# SCH_Poultry-Farm-Prediction-Models-_Fiel.net
KiCad netlist of a schematic drawn in EasyEDA
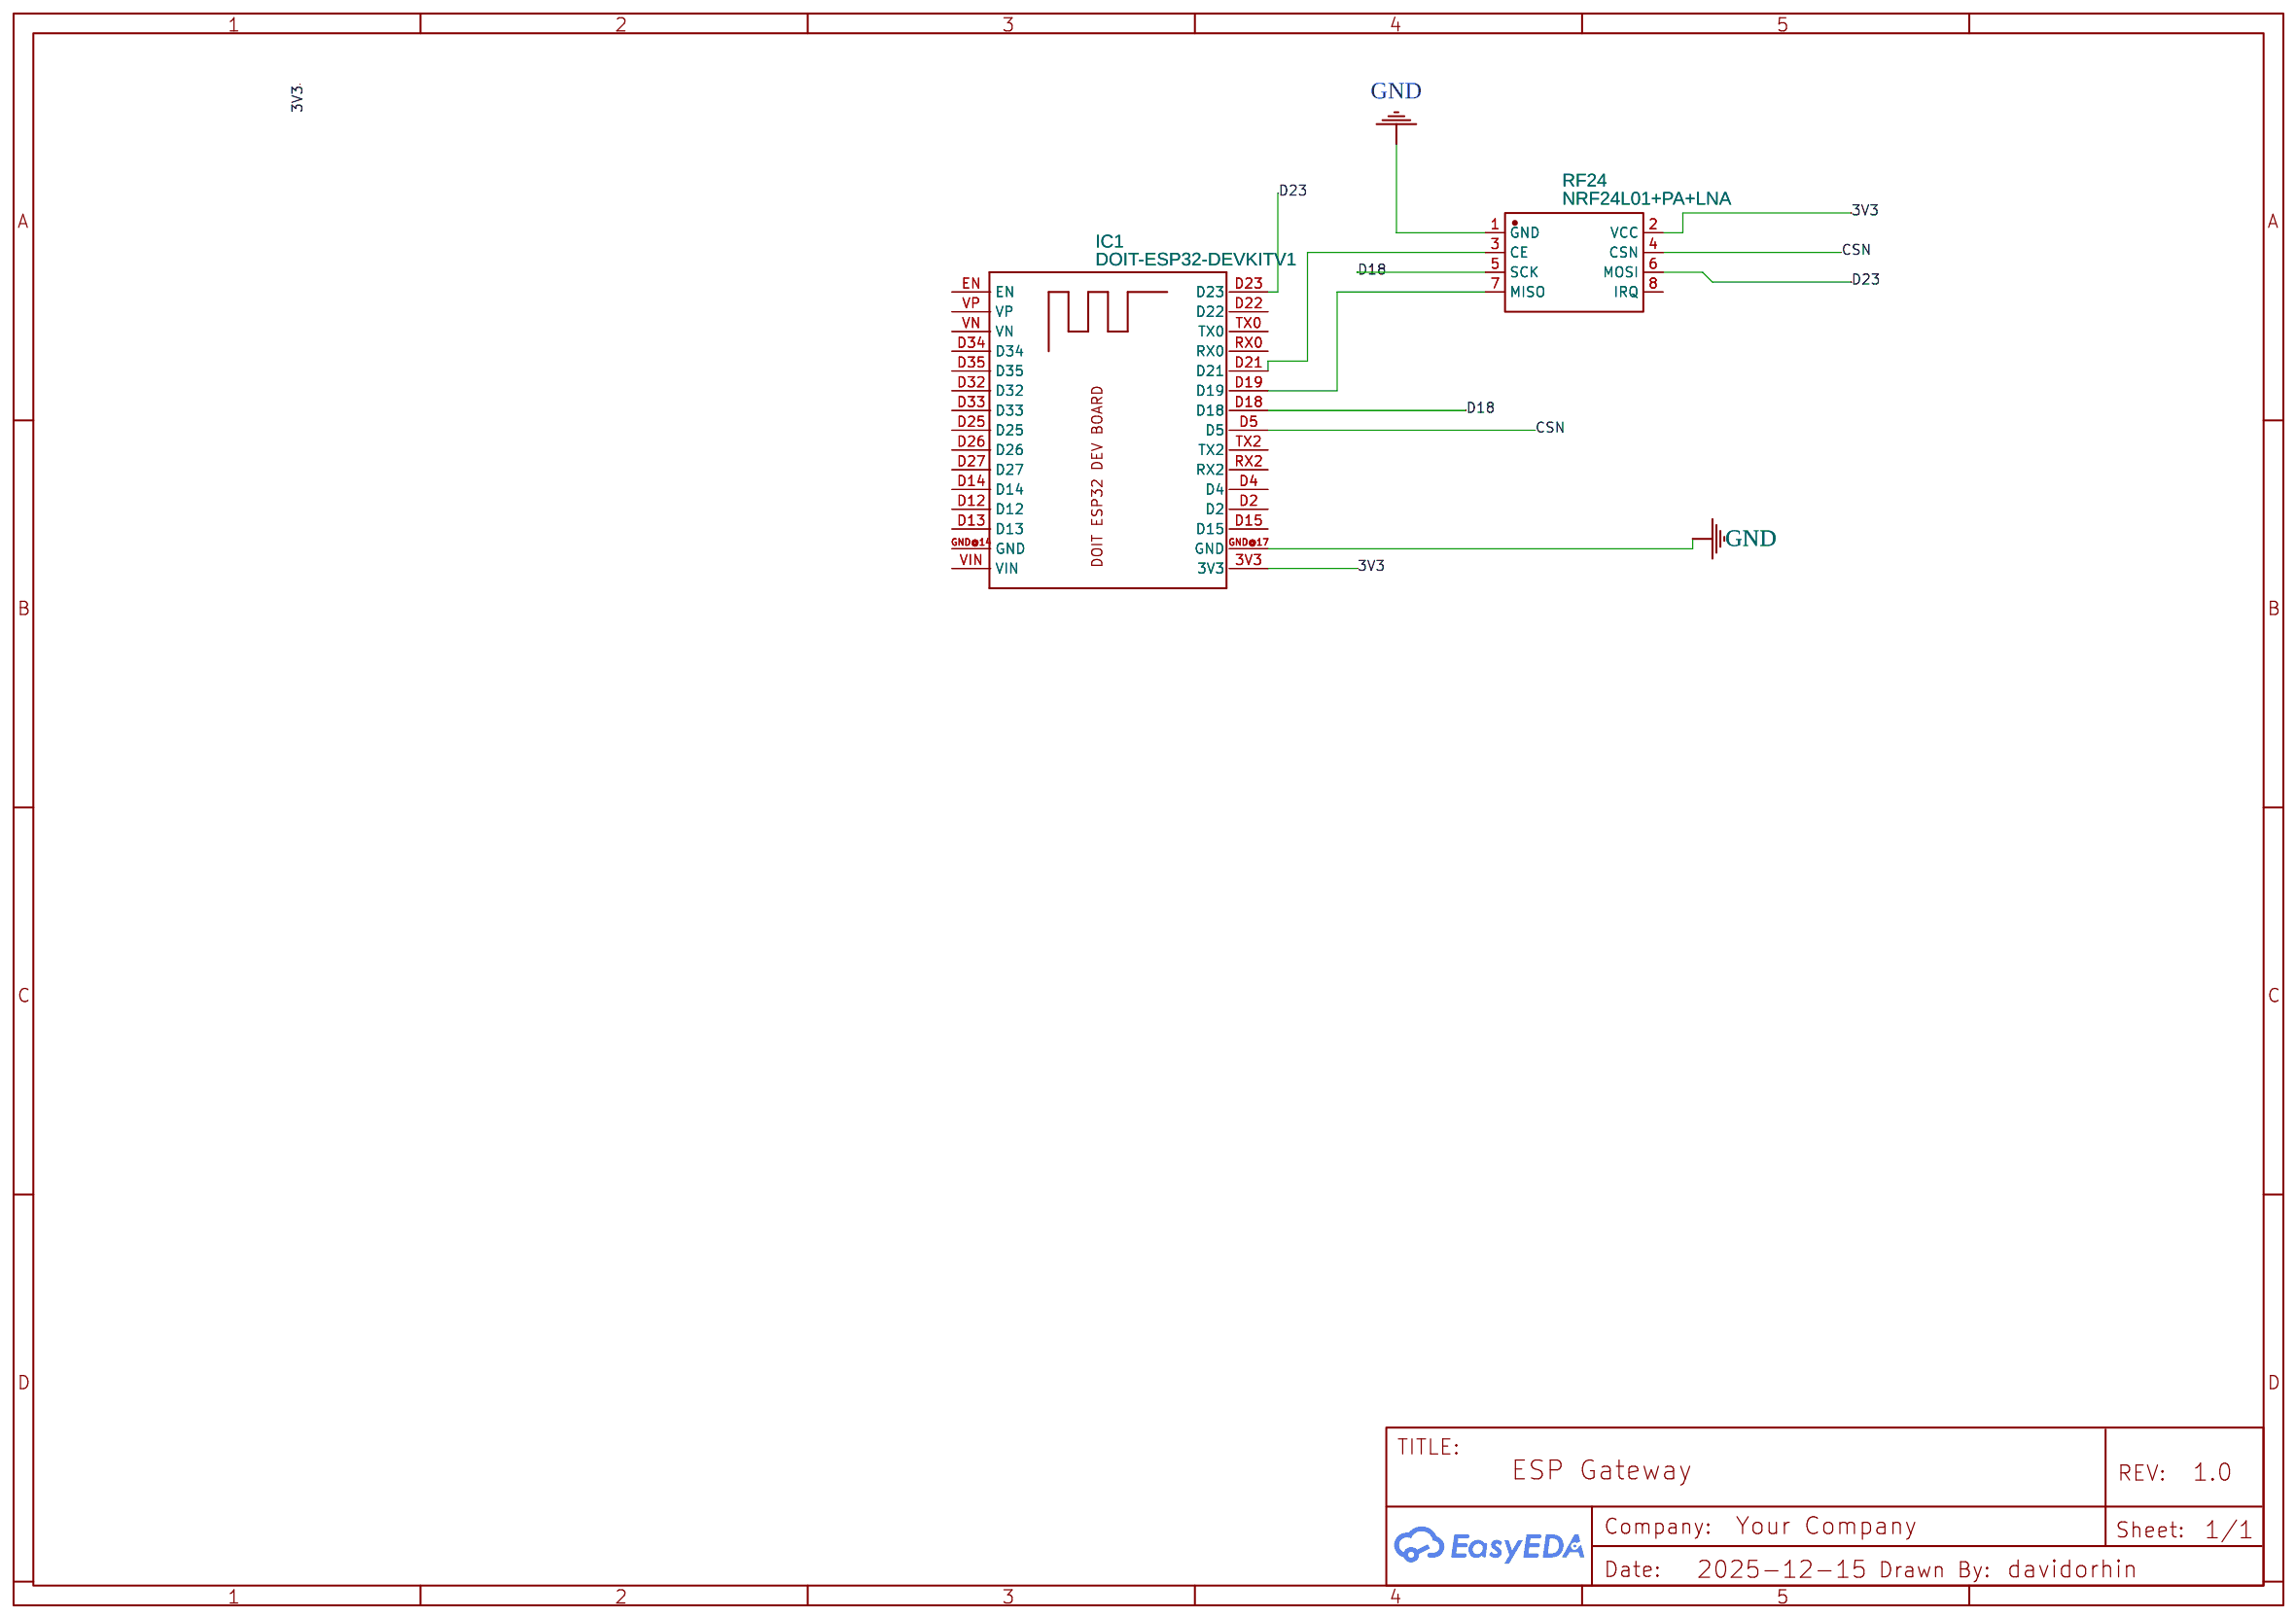
[diagram p0: Gateway Esp 32]
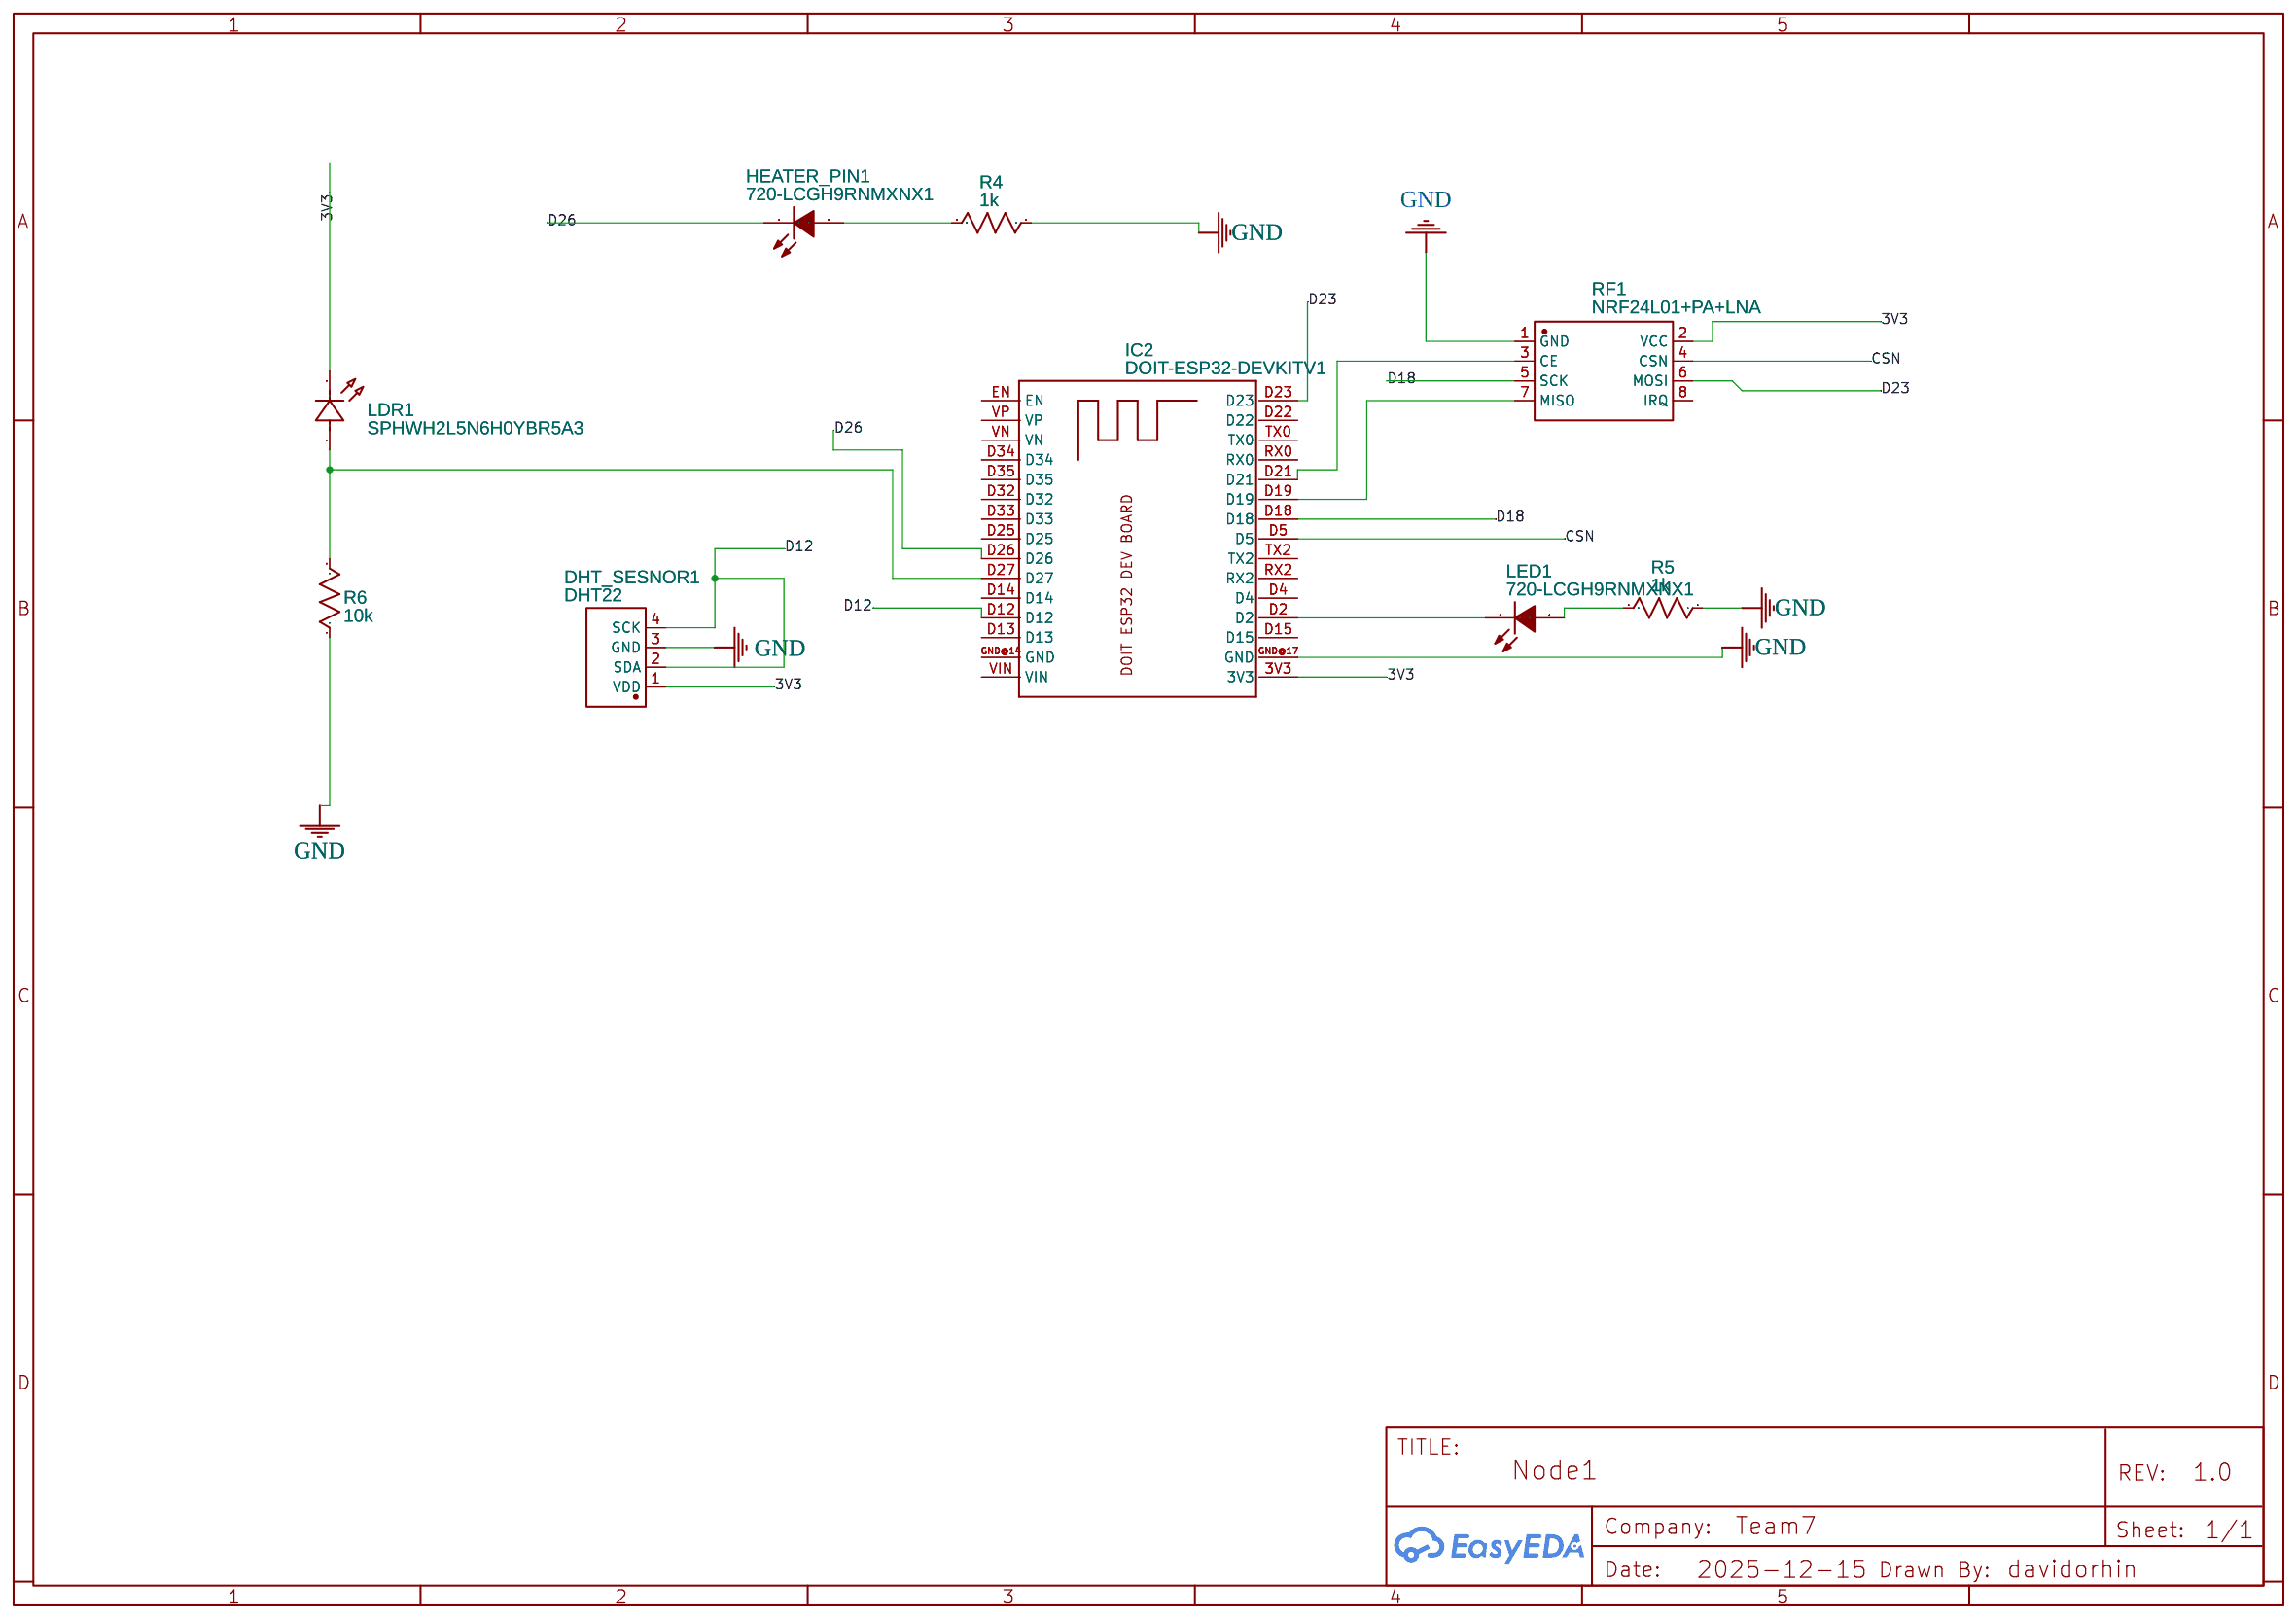
[diagram p1: Field Nodes Esp 33]

(export (version "E")
  (design (tool "Eeschema 10.0.6"))
  (components
    (comp (ref "IC1") (value "DOIT-ESP32-DEVKITV1") (libsource (lib "") (part "DOIT-ESP32-DEVKITV1")))
    (comp (ref "RF24")
      (value "NRF24L01+PA+LNA")
      (fields (field (name "Manufacturer Part") "nRF24L01+PA+LNA"))
      (libsource (lib "") (part "NRF24L01+PA+LNA"))
    )
    (comp (ref "DHT_SESNOR1")
      (value "DHT22")
      (fields (field (name "Manufacturer") "HAIGU(广州海谷)"))
      (libsource (lib "") (part "DHT22"))
    )
    (comp (ref "HEATER_PIN1") (value "720-LCGH9RNMXNX1") (libsource (lib "") (part "720-LCGH9RNMXNX1_1")))
    (comp (ref "IC2") (value "DOIT-ESP32-DEVKITV1") (libsource (lib "") (part "DOIT-ESP32-DEVKITV1")))
    (comp (ref "LDR1")
      (value "SPHWH2L5N6H0YBR5A3")
      (fields (field (name "Manufacturer") "SAMSUNG(三星)"))
      (libsource (lib "") (part "SPHWH2L5N6H0YBR5A3"))
    )
    (comp (ref "LED1") (value "720-LCGH9RNMXNX1") (libsource (lib "") (part "720-LCGH9RNMXNX1")))
    (comp (ref "R4") (value "1k") (libsource (lib "") (part "R_0603_US_1")))
    (comp (ref "R5") (value "1k") (libsource (lib "") (part "R_0603_US_1")))
    (comp (ref "R6") (value "10k") (libsource (lib "") (part "R_0603_US")))
    (comp (ref "RF1")
      (value "NRF24L01+PA+LNA")
      (fields (field (name "Manufacturer Part") "nRF24L01+PA+LNA"))
      (libsource (lib "") (part "NRF24L01+PA+LNA"))
    )
  )
  (nets
    (net (code "1") (name "3V3") (class "Default")
      (node (ref "DHT_SESNOR1") (pin "1") (pinfunction "VDD_1") (pintype "unspecified"))
      (node (ref "IC1") (pin "3V3") (pinfunction "3V3_3V3") (pintype "bidirectional"))
      (node (ref "IC2") (pin "3V3") (pinfunction "3V3_3V3") (pintype "bidirectional"))
      (node (ref "LDR1") (pin "1") (pinfunction "C_1") (pintype "unspecified"))
      (node (ref "RF1") (pin "2") (pinfunction "VCC_2") (pintype "unspecified"))
      (node (ref "RF24") (pin "2") (pinfunction "VCC_2") (pintype "unspecified"))
    )
    (net (code "2") (name "CSN") (class "Default")
      (node (ref "IC1") (pin "D5") (pinfunction "D5_D5") (pintype "bidirectional"))
      (node (ref "IC2") (pin "D5") (pinfunction "D5_D5") (pintype "bidirectional"))
      (node (ref "RF1") (pin "4") (pinfunction "CSN_4") (pintype "unspecified"))
      (node (ref "RF24") (pin "4") (pinfunction "CSN_4") (pintype "unspecified"))
    )
    (net (code "3") (name "D12") (class "Default")
      (node (ref "DHT_SESNOR1") (pin "2") (pinfunction "SDA_2") (pintype "unspecified"))
      (node (ref "DHT_SESNOR1") (pin "4") (pinfunction "SCK_4") (pintype "unspecified"))
      (node (ref "IC2") (pin "D12") (pinfunction "D12_D12") (pintype "bidirectional"))
    )
    (net (code "4") (name "D18") (class "Default")
      (node (ref "IC1") (pin "D18") (pinfunction "D18_D18") (pintype "bidirectional"))
      (node (ref "IC2") (pin "D18") (pinfunction "D18_D18") (pintype "bidirectional"))
      (node (ref "RF1") (pin "5") (pinfunction "SCK_5") (pintype "unspecified"))
      (node (ref "RF24") (pin "5") (pinfunction "SCK_5") (pintype "unspecified"))
    )
    (net (code "5") (name "D23") (class "Default")
      (node (ref "IC1") (pin "D23") (pinfunction "D23_D23") (pintype "bidirectional"))
      (node (ref "IC2") (pin "D23") (pinfunction "D23_D23") (pintype "bidirectional"))
      (node (ref "RF1") (pin "6") (pinfunction "MOSI_6") (pintype "unspecified"))
      (node (ref "RF24") (pin "6") (pinfunction "MOSI_6") (pintype "unspecified"))
    )
    (net (code "6") (name "D26") (class "Default")
      (node (ref "HEATER_PIN1") (pin "1") (pinfunction "K_1") (pintype "unspecified"))
      (node (ref "IC2") (pin "D26") (pinfunction "D26_D26") (pintype "bidirectional"))
    )
    (net (code "7") (name "GND") (class "Default")
      (node (ref "DHT_SESNOR1") (pin "3") (pinfunction "GND_3") (pintype "unspecified"))
      (node (ref "IC1") (pin "GND@17") (pinfunction "GND_GND@17") (pintype "bidirectional"))
      (node (ref "IC2") (pin "GND@17") (pinfunction "GND_GND@17") (pintype "bidirectional"))
      (node (ref "R4") (pin "1") (pinfunction "1_1") (pintype "unspecified"))
      (node (ref "R5") (pin "1") (pinfunction "1_1") (pintype "unspecified"))
      (node (ref "R6") (pin "1") (pinfunction "1_1") (pintype "unspecified"))
      (node (ref "RF1") (pin "1") (pinfunction "GND_1") (pintype "unspecified"))
      (node (ref "RF24") (pin "1") (pinfunction "GND_1") (pintype "unspecified"))
    )
    (net (code "8") (name "Net-(HEATER_PIN1-A)") (class "Default")
      (node (ref "HEATER_PIN1") (pin "2") (pinfunction "A_2") (pintype "unspecified"))
      (node (ref "R4") (pin "2") (pinfunction "2_2") (pintype "unspecified"))
    )
    (net (code "9") (name "Net-(LDR1-A)") (class "Default")
      (node (ref "IC2") (pin "D27") (pinfunction "D27_D27") (pintype "bidirectional"))
      (node (ref "LDR1") (pin "2") (pinfunction "A_2") (pintype "unspecified"))
      (node (ref "R6") (pin "2") (pinfunction "2_2") (pintype "unspecified"))
    )
    (net (code "10") (name "Net-(LED1-A)") (class "Default")
      (node (ref "LED1") (pin "2") (pinfunction "A_2") (pintype "unspecified"))
      (node (ref "R5") (pin "2") (pinfunction "2_2") (pintype "unspecified"))
    )
    (net (code "11") (name "Net-(LED1-K)") (class "Default")
      (node (ref "IC2") (pin "D2") (pinfunction "D2_D2") (pintype "bidirectional"))
      (node (ref "LED1") (pin "1") (pinfunction "K_1") (pintype "unspecified"))
    )
    (net (code "12") (name "Net-(RF1-CE)") (class "Default")
      (node (ref "IC2") (pin "D21") (pinfunction "D21_D21") (pintype "bidirectional"))
      (node (ref "RF1") (pin "3") (pinfunction "CE_3") (pintype "unspecified"))
    )
    (net (code "13") (name "Net-(RF1-MISO)") (class "Default")
      (node (ref "IC2") (pin "D19") (pinfunction "D19_D19") (pintype "bidirectional"))
      (node (ref "RF1") (pin "7") (pinfunction "MISO_7") (pintype "unspecified"))
    )
    (net (code "14") (name "Net-(RF24-CE)") (class "Default")
      (node (ref "IC1") (pin "D21") (pinfunction "D21_D21") (pintype "bidirectional"))
      (node (ref "RF24") (pin "3") (pinfunction "CE_3") (pintype "unspecified"))
    )
    (net (code "15") (name "Net-(RF24-MISO)") (class "Default")
      (node (ref "IC1") (pin "D19") (pinfunction "D19_D19") (pintype "bidirectional"))
      (node (ref "RF24") (pin "7") (pinfunction "MISO_7") (pintype "unspecified"))
    )
    (net (code "16") (name "unconnected-(IC1-GND-PadGND@14)") (class "Default")
      (node (ref "IC1") (pin "GND@14") (pinfunction "GND_GND@14") (pintype "bidirectional"))
    )
    (net (code "17") (name "unconnected-(IC1-PadD2)") (class "Default")
      (node (ref "IC1") (pin "D2") (pinfunction "D2_D2") (pintype "bidirectional"))
    )
    (net (code "18") (name "unconnected-(IC1-PadD4)") (class "Default")
      (node (ref "IC1") (pin "D4") (pinfunction "D4_D4") (pintype "bidirectional"))
    )
    (net (code "19") (name "unconnected-(IC1-PadD12)") (class "Default")
      (node (ref "IC1") (pin "D12") (pinfunction "D12_D12") (pintype "bidirectional"))
    )
    (net (code "20") (name "unconnected-(IC1-PadD13)") (class "Default")
      (node (ref "IC1") (pin "D13") (pinfunction "D13_D13") (pintype "bidirectional"))
    )
    (net (code "21") (name "unconnected-(IC1-PadD14)") (class "Default")
      (node (ref "IC1") (pin "D14") (pinfunction "D14_D14") (pintype "bidirectional"))
    )
    (net (code "22") (name "unconnected-(IC1-PadD15)") (class "Default")
      (node (ref "IC1") (pin "D15") (pinfunction "D15_D15") (pintype "bidirectional"))
    )
    (net (code "23") (name "unconnected-(IC1-PadD22)") (class "Default")
      (node (ref "IC1") (pin "D22") (pinfunction "D22_D22") (pintype "bidirectional"))
    )
    (net (code "24") (name "unconnected-(IC1-PadD25)") (class "Default")
      (node (ref "IC1") (pin "D25") (pinfunction "D25_D25") (pintype "bidirectional"))
    )
    (net (code "25") (name "unconnected-(IC1-PadD26)") (class "Default")
      (node (ref "IC1") (pin "D26") (pinfunction "D26_D26") (pintype "bidirectional"))
    )
    (net (code "26") (name "unconnected-(IC1-PadD27)") (class "Default")
      (node (ref "IC1") (pin "D27") (pinfunction "D27_D27") (pintype "bidirectional"))
    )
    (net (code "27") (name "unconnected-(IC1-PadD32)") (class "Default")
      (node (ref "IC1") (pin "D32") (pinfunction "D32_D32") (pintype "bidirectional"))
    )
    (net (code "28") (name "unconnected-(IC1-PadD33)") (class "Default")
      (node (ref "IC1") (pin "D33") (pinfunction "D33_D33") (pintype "bidirectional"))
    )
    (net (code "29") (name "unconnected-(IC1-PadD34)") (class "Default")
      (node (ref "IC1") (pin "D34") (pinfunction "D34_D34") (pintype "bidirectional"))
    )
    (net (code "30") (name "unconnected-(IC1-PadD35)") (class "Default")
      (node (ref "IC1") (pin "D35") (pinfunction "D35_D35") (pintype "bidirectional"))
    )
    (net (code "31") (name "unconnected-(IC1-PadEN)") (class "Default")
      (node (ref "IC1") (pin "EN") (pinfunction "EN_EN") (pintype "bidirectional"))
    )
    (net (code "32") (name "unconnected-(IC1-PadRX0)") (class "Default")
      (node (ref "IC1") (pin "RX0") (pinfunction "RX0_RX0") (pintype "bidirectional"))
    )
    (net (code "33") (name "unconnected-(IC1-PadRX2)") (class "Default")
      (node (ref "IC1") (pin "RX2") (pinfunction "RX2_RX2") (pintype "bidirectional"))
    )
    (net (code "34") (name "unconnected-(IC1-PadTX0)") (class "Default")
      (node (ref "IC1") (pin "TX0") (pinfunction "TX0_TX0") (pintype "bidirectional"))
    )
    (net (code "35") (name "unconnected-(IC1-PadTX2)") (class "Default")
      (node (ref "IC1") (pin "TX2") (pinfunction "TX2_TX2") (pintype "bidirectional"))
    )
    (net (code "36") (name "unconnected-(IC1-PadVIN)") (class "Default")
      (node (ref "IC1") (pin "VIN") (pinfunction "VIN_VIN") (pintype "bidirectional"))
    )
    (net (code "37") (name "unconnected-(IC1-PadVN)") (class "Default")
      (node (ref "IC1") (pin "VN") (pinfunction "VN_VN") (pintype "bidirectional"))
    )
    (net (code "38") (name "unconnected-(IC1-PadVP)") (class "Default")
      (node (ref "IC1") (pin "VP") (pinfunction "VP_VP") (pintype "bidirectional"))
    )
    (net (code "39") (name "unconnected-(IC2-GND-PadGND@14)") (class "Default")
      (node (ref "IC2") (pin "GND@14") (pinfunction "GND_GND@14") (pintype "bidirectional"))
    )
    (net (code "40") (name "unconnected-(IC2-PadD4)") (class "Default")
      (node (ref "IC2") (pin "D4") (pinfunction "D4_D4") (pintype "bidirectional"))
    )
    (net (code "41") (name "unconnected-(IC2-PadD13)") (class "Default")
      (node (ref "IC2") (pin "D13") (pinfunction "D13_D13") (pintype "bidirectional"))
    )
    (net (code "42") (name "unconnected-(IC2-PadD14)") (class "Default")
      (node (ref "IC2") (pin "D14") (pinfunction "D14_D14") (pintype "bidirectional"))
    )
    (net (code "43") (name "unconnected-(IC2-PadD15)") (class "Default")
      (node (ref "IC2") (pin "D15") (pinfunction "D15_D15") (pintype "bidirectional"))
    )
    (net (code "44") (name "unconnected-(IC2-PadD22)") (class "Default")
      (node (ref "IC2") (pin "D22") (pinfunction "D22_D22") (pintype "bidirectional"))
    )
    (net (code "45") (name "unconnected-(IC2-PadD25)") (class "Default")
      (node (ref "IC2") (pin "D25") (pinfunction "D25_D25") (pintype "bidirectional"))
    )
    (net (code "46") (name "unconnected-(IC2-PadD32)") (class "Default")
      (node (ref "IC2") (pin "D32") (pinfunction "D32_D32") (pintype "bidirectional"))
    )
    (net (code "47") (name "unconnected-(IC2-PadD33)") (class "Default")
      (node (ref "IC2") (pin "D33") (pinfunction "D33_D33") (pintype "bidirectional"))
    )
    (net (code "48") (name "unconnected-(IC2-PadD34)") (class "Default")
      (node (ref "IC2") (pin "D34") (pinfunction "D34_D34") (pintype "bidirectional"))
    )
    (net (code "49") (name "unconnected-(IC2-PadD35)") (class "Default")
      (node (ref "IC2") (pin "D35") (pinfunction "D35_D35") (pintype "bidirectional"))
    )
    (net (code "50") (name "unconnected-(IC2-PadEN)") (class "Default")
      (node (ref "IC2") (pin "EN") (pinfunction "EN_EN") (pintype "bidirectional"))
    )
    (net (code "51") (name "unconnected-(IC2-PadRX0)") (class "Default")
      (node (ref "IC2") (pin "RX0") (pinfunction "RX0_RX0") (pintype "bidirectional"))
    )
    (net (code "52") (name "unconnected-(IC2-PadRX2)") (class "Default")
      (node (ref "IC2") (pin "RX2") (pinfunction "RX2_RX2") (pintype "bidirectional"))
    )
    (net (code "53") (name "unconnected-(IC2-PadTX0)") (class "Default")
      (node (ref "IC2") (pin "TX0") (pinfunction "TX0_TX0") (pintype "bidirectional"))
    )
    (net (code "54") (name "unconnected-(IC2-PadTX2)") (class "Default")
      (node (ref "IC2") (pin "TX2") (pinfunction "TX2_TX2") (pintype "bidirectional"))
    )
    (net (code "55") (name "unconnected-(IC2-PadVIN)") (class "Default")
      (node (ref "IC2") (pin "VIN") (pinfunction "VIN_VIN") (pintype "bidirectional"))
    )
    (net (code "56") (name "unconnected-(IC2-PadVN)") (class "Default")
      (node (ref "IC2") (pin "VN") (pinfunction "VN_VN") (pintype "bidirectional"))
    )
    (net (code "57") (name "unconnected-(IC2-PadVP)") (class "Default")
      (node (ref "IC2") (pin "VP") (pinfunction "VP_VP") (pintype "bidirectional"))
    )
    (net (code "58") (name "unconnected-(RF1-IRQ-Pad8)") (class "Default")
      (node (ref "RF1") (pin "8") (pinfunction "IRQ_8") (pintype "unspecified"))
    )
    (net (code "59") (name "unconnected-(RF24-IRQ-Pad8)") (class "Default")
      (node (ref "RF24") (pin "8") (pinfunction "IRQ_8") (pintype "unspecified"))
    )
  )
)
